# driver_03_12_2018.net
KiCad netlist of a schematic drawn in EAGLE
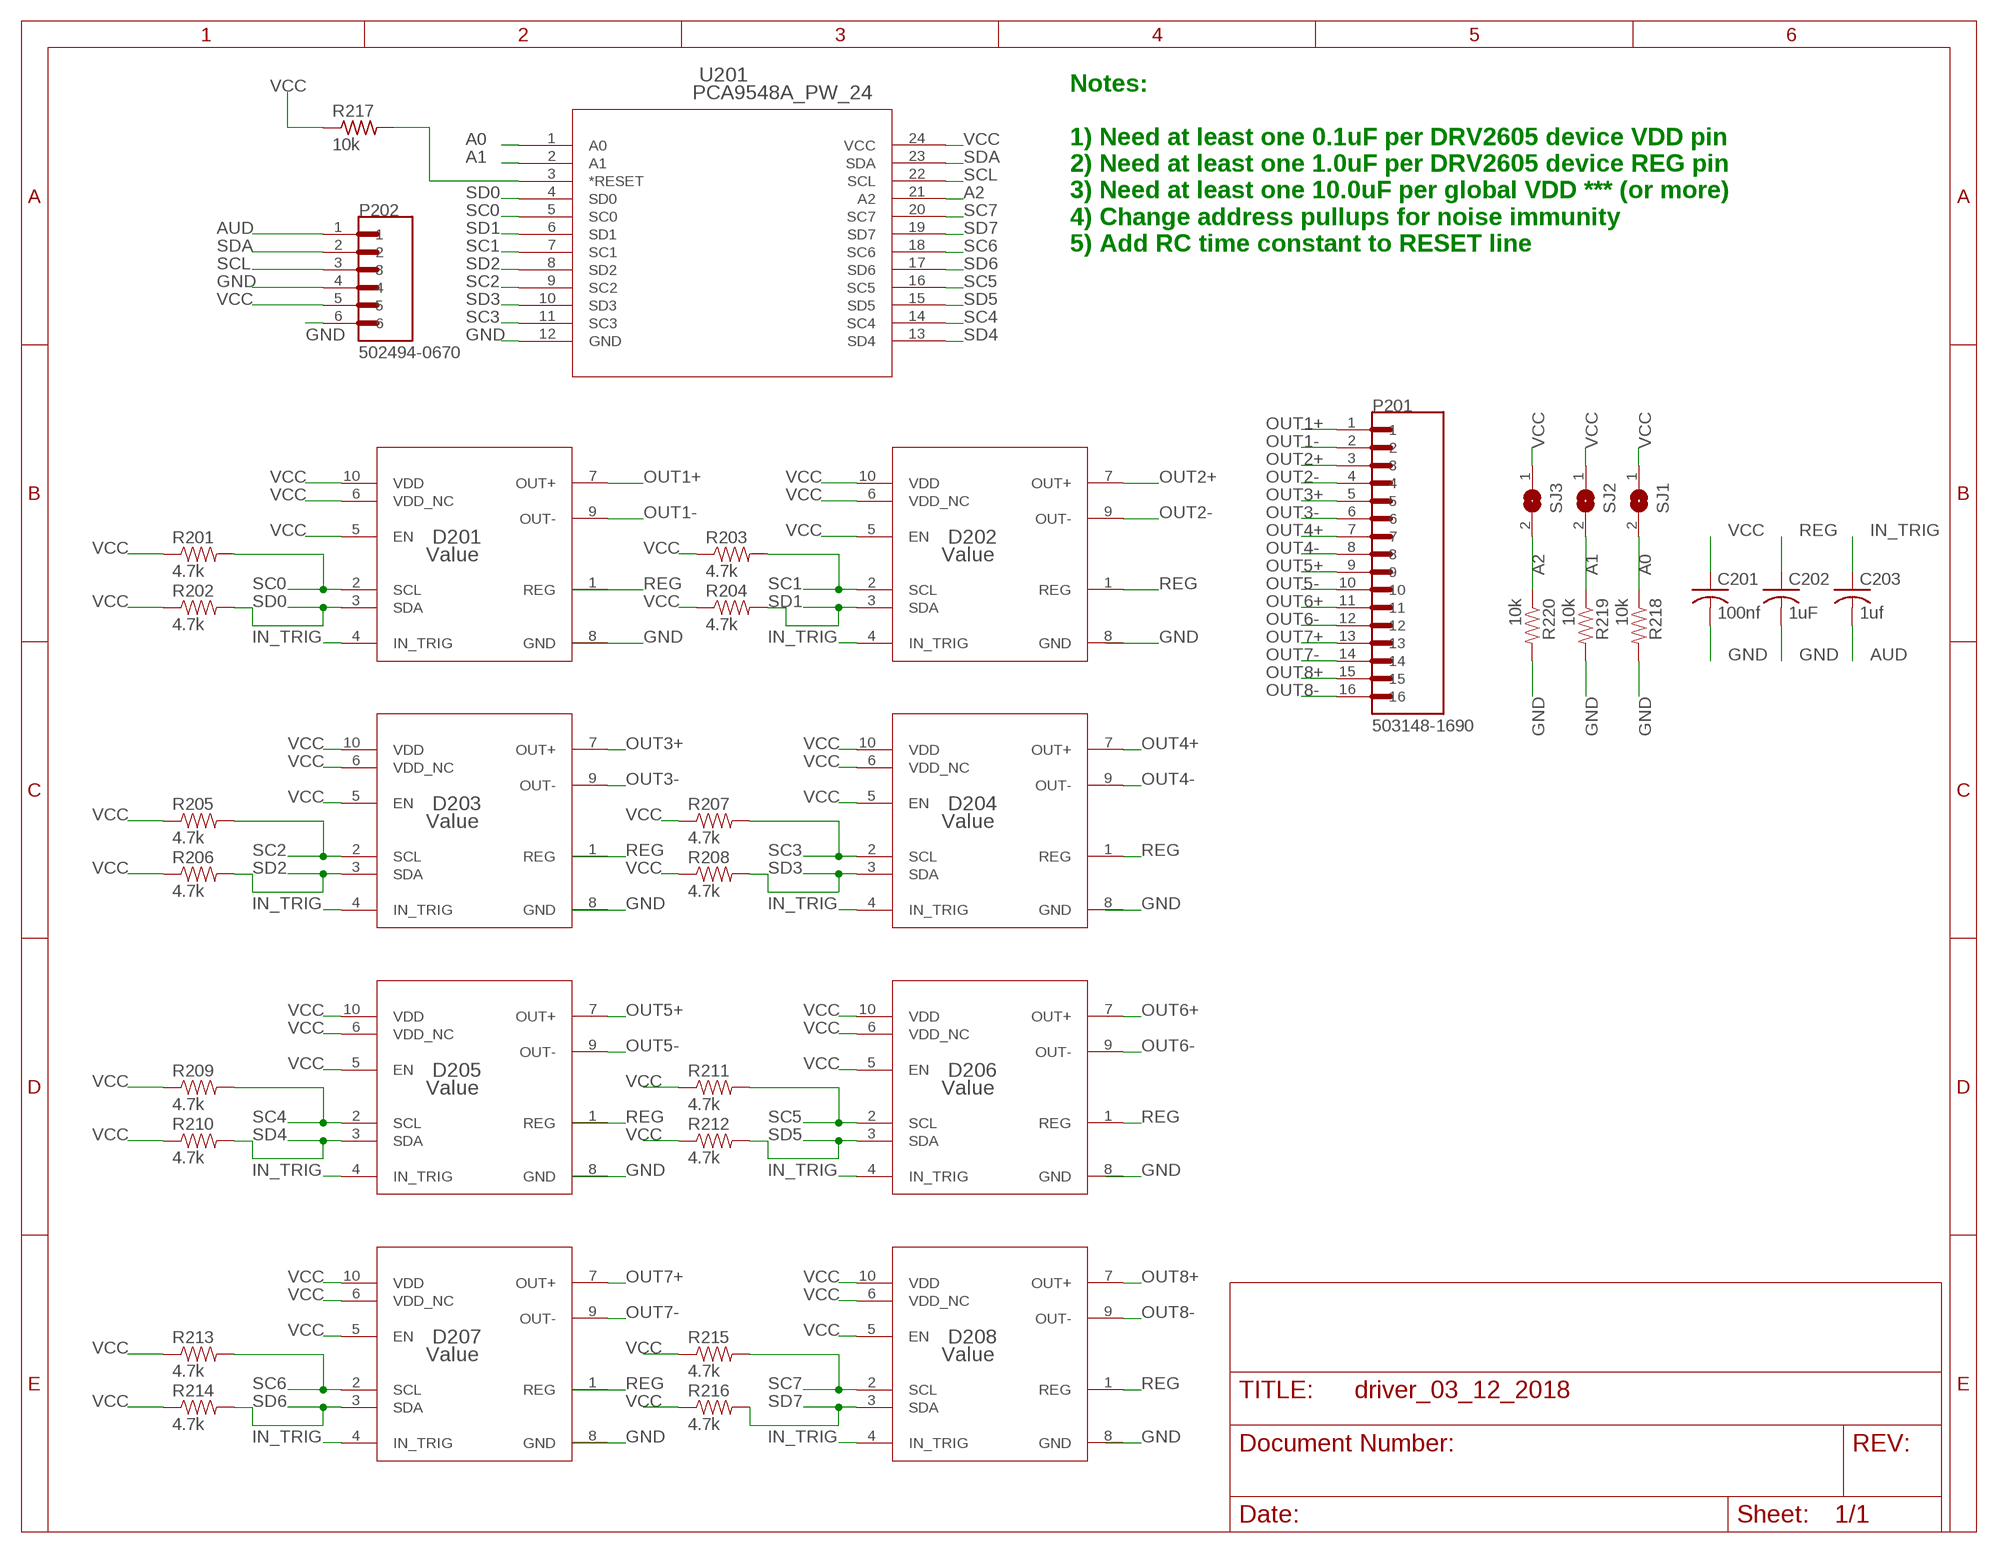
[diagram p0: schematic, sheet 1]

(export (version "E")
  (design (tool "Eeschema 10.0.6"))
  (components
    (comp (ref "C201")
      (value "100nf")
      (footprint "eagle-import:C0603")
      (libsource (lib "eagle-import") (part "C-USC0603"))
    )
    (comp (ref "C202")
      (value "1uF")
      (footprint "eagle-import:C0603")
      (libsource (lib "eagle-import") (part "C-USC0603"))
    )
    (comp (ref "C203")
      (value "1uf")
      (footprint "eagle-import:C0603")
      (libsource (lib "eagle-import") (part "C-USC0603"))
    )
    (comp (ref "D201")
      (value "Value")
      (footprint "eagle-import:DGS0010A")
      (fields (field (name "MANUFACTURER") "Texas Instruments") (field (name "PARTNUMBER") "DRV2605LDGS"))
      (libsource (lib "eagle-import") (part "DRV2605LDGSR"))
    )
    (comp (ref "D202")
      (value "Value")
      (footprint "eagle-import:DGS0010A")
      (fields (field (name "MANUFACTURER") "Texas Instruments") (field (name "PARTNUMBER") "DRV2605LDGS"))
      (libsource (lib "eagle-import") (part "DRV2605LDGSR"))
    )
    (comp (ref "D203")
      (value "Value")
      (footprint "eagle-import:DGS0010A")
      (fields (field (name "MANUFACTURER") "Texas Instruments") (field (name "PARTNUMBER") "DRV2605LDGS"))
      (libsource (lib "eagle-import") (part "DRV2605LDGSR"))
    )
    (comp (ref "D204")
      (value "Value")
      (footprint "eagle-import:DGS0010A")
      (fields (field (name "MANUFACTURER") "Texas Instruments") (field (name "PARTNUMBER") "DRV2605LDGS"))
      (libsource (lib "eagle-import") (part "DRV2605LDGSR"))
    )
    (comp (ref "D205")
      (value "Value")
      (footprint "eagle-import:DGS0010A")
      (fields (field (name "MANUFACTURER") "Texas Instruments") (field (name "PARTNUMBER") "DRV2605LDGS"))
      (libsource (lib "eagle-import") (part "DRV2605LDGSR"))
    )
    (comp (ref "D206")
      (value "Value")
      (footprint "eagle-import:DGS0010A")
      (fields (field (name "MANUFACTURER") "Texas Instruments") (field (name "PARTNUMBER") "DRV2605LDGS"))
      (libsource (lib "eagle-import") (part "DRV2605LDGSR"))
    )
    (comp (ref "D207")
      (value "Value")
      (footprint "eagle-import:DGS0010A")
      (fields (field (name "MANUFACTURER") "Texas Instruments") (field (name "PARTNUMBER") "DRV2605LDGS"))
      (libsource (lib "eagle-import") (part "DRV2605LDGSR"))
    )
    (comp (ref "D208")
      (value "Value")
      (footprint "eagle-import:DGS0010A")
      (fields (field (name "MANUFACTURER") "Texas Instruments") (field (name "PARTNUMBER") "DRV2605LDGS"))
      (libsource (lib "eagle-import") (part "DRV2605LDGSR"))
    )
    (comp (ref "P201")
      (value "503148-1690")
      (footprint "eagle-import:MOLEX_503148-1690")
      (fields (field (name "MF") "Molex"))
      (libsource (lib "eagle-import") (part "503148-1690"))
    )
    (comp (ref "P202")
      (value "502494-0670")
      (footprint "eagle-import:MOLEX_502494-0670")
      (fields (field (name "MF") "Molex"))
      (libsource (lib "eagle-import") (part "502494-0670"))
    )
    (comp (ref "R201")
      (value "4.7k")
      (footprint "eagle-import:EIA-0402")
      (libsource (lib "eagle-import") (part "RESISTOR0402-TYP"))
    )
    (comp (ref "R202")
      (value "4.7k")
      (footprint "eagle-import:EIA-0402")
      (libsource (lib "eagle-import") (part "RESISTOR0402-TYP"))
    )
    (comp (ref "R203")
      (value "4.7k")
      (footprint "eagle-import:EIA-0402")
      (libsource (lib "eagle-import") (part "RESISTOR0402-TYP"))
    )
    (comp (ref "R204")
      (value "4.7k")
      (footprint "eagle-import:EIA-0402")
      (libsource (lib "eagle-import") (part "RESISTOR0402-TYP"))
    )
    (comp (ref "R205")
      (value "4.7k")
      (footprint "eagle-import:EIA-0402")
      (libsource (lib "eagle-import") (part "RESISTOR0402-TYP"))
    )
    (comp (ref "R206")
      (value "4.7k")
      (footprint "eagle-import:EIA-0402")
      (libsource (lib "eagle-import") (part "RESISTOR0402-TYP"))
    )
    (comp (ref "R207")
      (value "4.7k")
      (footprint "eagle-import:EIA-0402")
      (libsource (lib "eagle-import") (part "RESISTOR0402-TYP"))
    )
    (comp (ref "R208")
      (value "4.7k")
      (footprint "eagle-import:EIA-0402")
      (libsource (lib "eagle-import") (part "RESISTOR0402-TYP"))
    )
    (comp (ref "R209")
      (value "4.7k")
      (footprint "eagle-import:EIA-0402")
      (libsource (lib "eagle-import") (part "RESISTOR0402-TYP"))
    )
    (comp (ref "R210")
      (value "4.7k")
      (footprint "eagle-import:EIA-0402")
      (libsource (lib "eagle-import") (part "RESISTOR0402-TYP"))
    )
    (comp (ref "R211")
      (value "4.7k")
      (footprint "eagle-import:EIA-0402")
      (libsource (lib "eagle-import") (part "RESISTOR0402-TYP"))
    )
    (comp (ref "R212")
      (value "4.7k")
      (footprint "eagle-import:EIA-0402")
      (libsource (lib "eagle-import") (part "RESISTOR0402-TYP"))
    )
    (comp (ref "R213")
      (value "4.7k")
      (footprint "eagle-import:EIA-0402")
      (libsource (lib "eagle-import") (part "RESISTOR0402-TYP"))
    )
    (comp (ref "R214")
      (value "4.7k")
      (footprint "eagle-import:EIA-0402")
      (libsource (lib "eagle-import") (part "RESISTOR0402-TYP"))
    )
    (comp (ref "R215")
      (value "4.7k")
      (footprint "eagle-import:EIA-0402")
      (libsource (lib "eagle-import") (part "RESISTOR0402-TYP"))
    )
    (comp (ref "R216")
      (value "4.7k")
      (footprint "eagle-import:EIA-0402")
      (libsource (lib "eagle-import") (part "RESISTOR0402-TYP"))
    )
    (comp (ref "R217")
      (value "10k")
      (footprint "eagle-import:R0402")
      (libsource (lib "eagle-import") (part "R-US_R0402"))
    )
    (comp (ref "R218")
      (value "10k")
      (footprint "eagle-import:EIA-0402")
      (libsource (lib "eagle-import") (part "RESISTOR0402-TYP"))
    )
    (comp (ref "R219")
      (value "10k")
      (footprint "eagle-import:EIA-0402")
      (libsource (lib "eagle-import") (part "RESISTOR0402-TYP"))
    )
    (comp (ref "R220")
      (value "10k")
      (footprint "eagle-import:EIA-0402")
      (libsource (lib "eagle-import") (part "RESISTOR0402-TYP"))
    )
    (comp (ref "SJ1") (value "SJ") (footprint "eagle-import:SJ") (libsource (lib "eagle-import") (part "SJ")))
    (comp (ref "SJ2") (value "SJ") (footprint "eagle-import:SJ") (libsource (lib "eagle-import") (part "SJ")))
    (comp (ref "SJ3") (value "SJ") (footprint "eagle-import:SJ") (libsource (lib "eagle-import") (part "SJ")))
    (comp (ref "U201")
      (value "PCA9548A_PW_24")
      (footprint "eagle-import:PW24")
      (fields
        (field (name "GENERIC_PART_NUMBER") "PCA9548A")
        (field (name "MANUFACTURER") "Texas Instruments")
        (field (name "MANUFACTURER_PART_NUMBER") "pca9548a_pw_24")
      )
      (libsource (lib "eagle-import") (part "PCA9548A_PW_24"))
    )
  )
  (nets
    (net (code "1") (name "/A0") (class "Default")
      (node (ref "R218") (pin "1") (pinfunction "1_1") (pintype "passive"))
      (node (ref "SJ1") (pin "2") (pinfunction "2_2") (pintype "passive"))
      (node (ref "U201") (pin "1") (pinfunction "A0_1") (pintype "input"))
    )
    (net (code "2") (name "/A1") (class "Default")
      (node (ref "R219") (pin "1") (pinfunction "1_1") (pintype "passive"))
      (node (ref "SJ2") (pin "2") (pinfunction "2_2") (pintype "passive"))
      (node (ref "U201") (pin "2") (pinfunction "A1_2") (pintype "input"))
    )
    (net (code "3") (name "/A2") (class "Default")
      (node (ref "R220") (pin "1") (pinfunction "1_1") (pintype "passive"))
      (node (ref "SJ3") (pin "2") (pinfunction "2_2") (pintype "passive"))
      (node (ref "U201") (pin "21") (pinfunction "A2_21") (pintype "input"))
    )
    (net (code "4") (name "/AUD") (class "Default")
      (node (ref "C203") (pin "2") (pinfunction "2_2") (pintype "passive"))
      (node (ref "P202") (pin "1") (pinfunction "1_1") (pintype "passive"))
    )
    (net (code "5") (name "/GND") (class "Default")
      (node (ref "C201") (pin "2") (pinfunction "2_2") (pintype "passive"))
      (node (ref "C202") (pin "2") (pinfunction "2_2") (pintype "passive"))
      (node (ref "D201") (pin "8") (pinfunction "GND_8") (pintype "power_in"))
      (node (ref "D202") (pin "8") (pinfunction "GND_8") (pintype "power_in"))
      (node (ref "D203") (pin "8") (pinfunction "GND_8") (pintype "power_in"))
      (node (ref "D204") (pin "8") (pinfunction "GND_8") (pintype "power_in"))
      (node (ref "D205") (pin "8") (pinfunction "GND_8") (pintype "power_in"))
      (node (ref "D206") (pin "8") (pinfunction "GND_8") (pintype "power_in"))
      (node (ref "D207") (pin "8") (pinfunction "GND_8") (pintype "power_in"))
      (node (ref "D208") (pin "8") (pinfunction "GND_8") (pintype "power_in"))
      (node (ref "P202") (pin "4") (pinfunction "4_4") (pintype "passive"))
      (node (ref "P202") (pin "6") (pinfunction "6_6") (pintype "passive"))
      (node (ref "R218") (pin "2") (pinfunction "2_2") (pintype "passive"))
      (node (ref "R219") (pin "2") (pinfunction "2_2") (pintype "passive"))
      (node (ref "R220") (pin "2") (pinfunction "2_2") (pintype "passive"))
      (node (ref "U201") (pin "12") (pinfunction "GND_12") (pintype "power_in"))
    )
    (net (code "6") (name "/IN_TRIG") (class "Default")
      (node (ref "C203") (pin "1") (pinfunction "1_1") (pintype "passive"))
      (node (ref "D201") (pin "4") (pinfunction "IN_TRIG_4") (pintype "input"))
      (node (ref "D202") (pin "4") (pinfunction "IN_TRIG_4") (pintype "input"))
      (node (ref "D203") (pin "4") (pinfunction "IN_TRIG_4") (pintype "input"))
      (node (ref "D204") (pin "4") (pinfunction "IN_TRIG_4") (pintype "input"))
      (node (ref "D205") (pin "4") (pinfunction "IN_TRIG_4") (pintype "input"))
      (node (ref "D206") (pin "4") (pinfunction "IN_TRIG_4") (pintype "input"))
      (node (ref "D207") (pin "4") (pinfunction "IN_TRIG_4") (pintype "input"))
      (node (ref "D208") (pin "4") (pinfunction "IN_TRIG_4") (pintype "input"))
    )
    (net (code "7") (name "/OUT1+") (class "Default")
      (node (ref "D201") (pin "7") (pinfunction "OUT+_7") (pintype "output"))
      (node (ref "P201") (pin "1") (pinfunction "1_1") (pintype "passive"))
    )
    (net (code "8") (name "/OUT1-") (class "Default")
      (node (ref "D201") (pin "9") (pinfunction "OUT-_9") (pintype "output"))
      (node (ref "P201") (pin "2") (pinfunction "2_2") (pintype "passive"))
    )
    (net (code "9") (name "/OUT2+") (class "Default")
      (node (ref "D202") (pin "7") (pinfunction "OUT+_7") (pintype "output"))
      (node (ref "P201") (pin "3") (pinfunction "3_3") (pintype "passive"))
    )
    (net (code "10") (name "/OUT2-") (class "Default")
      (node (ref "D202") (pin "9") (pinfunction "OUT-_9") (pintype "output"))
      (node (ref "P201") (pin "4") (pinfunction "4_4") (pintype "passive"))
    )
    (net (code "11") (name "/OUT3+") (class "Default")
      (node (ref "D203") (pin "7") (pinfunction "OUT+_7") (pintype "output"))
      (node (ref "P201") (pin "5") (pinfunction "5_5") (pintype "passive"))
    )
    (net (code "12") (name "/OUT3-") (class "Default")
      (node (ref "D203") (pin "9") (pinfunction "OUT-_9") (pintype "output"))
      (node (ref "P201") (pin "6") (pinfunction "6_6") (pintype "passive"))
    )
    (net (code "13") (name "/OUT4+") (class "Default")
      (node (ref "D204") (pin "7") (pinfunction "OUT+_7") (pintype "output"))
      (node (ref "P201") (pin "7") (pinfunction "7_7") (pintype "passive"))
    )
    (net (code "14") (name "/OUT4-") (class "Default")
      (node (ref "D204") (pin "9") (pinfunction "OUT-_9") (pintype "output"))
      (node (ref "P201") (pin "8") (pinfunction "8_8") (pintype "passive"))
    )
    (net (code "15") (name "/OUT5+") (class "Default")
      (node (ref "D205") (pin "7") (pinfunction "OUT+_7") (pintype "output"))
      (node (ref "P201") (pin "9") (pinfunction "9_9") (pintype "passive"))
    )
    (net (code "16") (name "/OUT5-") (class "Default")
      (node (ref "D205") (pin "9") (pinfunction "OUT-_9") (pintype "output"))
      (node (ref "P201") (pin "10") (pinfunction "10_10") (pintype "passive"))
    )
    (net (code "17") (name "/OUT6+") (class "Default")
      (node (ref "D206") (pin "7") (pinfunction "OUT+_7") (pintype "output"))
      (node (ref "P201") (pin "11") (pinfunction "11_11") (pintype "passive"))
    )
    (net (code "18") (name "/OUT6-") (class "Default")
      (node (ref "D206") (pin "9") (pinfunction "OUT-_9") (pintype "output"))
      (node (ref "P201") (pin "12") (pinfunction "12_12") (pintype "passive"))
    )
    (net (code "19") (name "/OUT7+") (class "Default")
      (node (ref "D207") (pin "7") (pinfunction "OUT+_7") (pintype "output"))
      (node (ref "P201") (pin "13") (pinfunction "13_13") (pintype "passive"))
    )
    (net (code "20") (name "/OUT7-") (class "Default")
      (node (ref "D207") (pin "9") (pinfunction "OUT-_9") (pintype "output"))
      (node (ref "P201") (pin "14") (pinfunction "14_14") (pintype "passive"))
    )
    (net (code "21") (name "/OUT8+") (class "Default")
      (node (ref "D208") (pin "7") (pinfunction "OUT+_7") (pintype "output"))
      (node (ref "P201") (pin "15") (pinfunction "15_15") (pintype "passive"))
    )
    (net (code "22") (name "/OUT8-") (class "Default")
      (node (ref "D208") (pin "9") (pinfunction "OUT-_9") (pintype "output"))
      (node (ref "P201") (pin "16") (pinfunction "16_16") (pintype "passive"))
    )
    (net (code "23") (name "/REG") (class "Default")
      (node (ref "C202") (pin "1") (pinfunction "1_1") (pintype "passive"))
      (node (ref "D201") (pin "1") (pinfunction "REG_1") (pintype "power_in"))
      (node (ref "D202") (pin "1") (pinfunction "REG_1") (pintype "power_in"))
      (node (ref "D203") (pin "1") (pinfunction "REG_1") (pintype "power_in"))
      (node (ref "D204") (pin "1") (pinfunction "REG_1") (pintype "power_in"))
      (node (ref "D205") (pin "1") (pinfunction "REG_1") (pintype "power_in"))
      (node (ref "D206") (pin "1") (pinfunction "REG_1") (pintype "power_in"))
      (node (ref "D207") (pin "1") (pinfunction "REG_1") (pintype "power_in"))
      (node (ref "D208") (pin "1") (pinfunction "REG_1") (pintype "power_in"))
    )
    (net (code "24") (name "/SC0") (class "Default")
      (node (ref "D201") (pin "2") (pinfunction "SCL_2") (pintype "input"))
      (node (ref "R201") (pin "2") (pinfunction "2_2") (pintype "passive"))
      (node (ref "U201") (pin "5") (pinfunction "SC0_5") (pintype "passive"))
    )
    (net (code "25") (name "/SC1") (class "Default")
      (node (ref "D202") (pin "2") (pinfunction "SCL_2") (pintype "input"))
      (node (ref "R203") (pin "2") (pinfunction "2_2") (pintype "passive"))
      (node (ref "U201") (pin "7") (pinfunction "SC1_7") (pintype "passive"))
    )
    (net (code "26") (name "/SC2") (class "Default")
      (node (ref "D203") (pin "2") (pinfunction "SCL_2") (pintype "input"))
      (node (ref "R205") (pin "2") (pinfunction "2_2") (pintype "passive"))
      (node (ref "U201") (pin "9") (pinfunction "SC2_9") (pintype "passive"))
    )
    (net (code "27") (name "/SC3") (class "Default")
      (node (ref "D204") (pin "2") (pinfunction "SCL_2") (pintype "input"))
      (node (ref "R207") (pin "2") (pinfunction "2_2") (pintype "passive"))
      (node (ref "U201") (pin "11") (pinfunction "SC3_11") (pintype "passive"))
    )
    (net (code "28") (name "/SC4") (class "Default")
      (node (ref "D205") (pin "2") (pinfunction "SCL_2") (pintype "input"))
      (node (ref "R209") (pin "2") (pinfunction "2_2") (pintype "passive"))
      (node (ref "U201") (pin "14") (pinfunction "SC4_14") (pintype "passive"))
    )
    (net (code "29") (name "/SC5") (class "Default")
      (node (ref "D206") (pin "2") (pinfunction "SCL_2") (pintype "input"))
      (node (ref "R211") (pin "2") (pinfunction "2_2") (pintype "passive"))
      (node (ref "U201") (pin "16") (pinfunction "SC5_16") (pintype "passive"))
    )
    (net (code "30") (name "/SC6") (class "Default")
      (node (ref "D207") (pin "2") (pinfunction "SCL_2") (pintype "input"))
      (node (ref "R213") (pin "2") (pinfunction "2_2") (pintype "passive"))
      (node (ref "U201") (pin "18") (pinfunction "SC6_18") (pintype "passive"))
    )
    (net (code "31") (name "/SC7") (class "Default")
      (node (ref "D208") (pin "2") (pinfunction "SCL_2") (pintype "input"))
      (node (ref "R215") (pin "2") (pinfunction "2_2") (pintype "passive"))
      (node (ref "U201") (pin "20") (pinfunction "SC7_20") (pintype "passive"))
    )
    (net (code "32") (name "/SCL") (class "Default")
      (node (ref "P202") (pin "3") (pinfunction "3_3") (pintype "passive"))
      (node (ref "U201") (pin "22") (pinfunction "SCL_22") (pintype "passive"))
    )
    (net (code "33") (name "/SD0") (class "Default")
      (node (ref "D201") (pin "3") (pinfunction "SDA_3") (pintype "bidirectional"))
      (node (ref "R202") (pin "2") (pinfunction "2_2") (pintype "passive"))
      (node (ref "U201") (pin "4") (pinfunction "SD0_4") (pintype "passive"))
    )
    (net (code "34") (name "/SD1") (class "Default")
      (node (ref "D202") (pin "3") (pinfunction "SDA_3") (pintype "bidirectional"))
      (node (ref "R204") (pin "2") (pinfunction "2_2") (pintype "passive"))
      (node (ref "U201") (pin "6") (pinfunction "SD1_6") (pintype "passive"))
    )
    (net (code "35") (name "/SD2") (class "Default")
      (node (ref "D203") (pin "3") (pinfunction "SDA_3") (pintype "bidirectional"))
      (node (ref "R206") (pin "2") (pinfunction "2_2") (pintype "passive"))
      (node (ref "U201") (pin "8") (pinfunction "SD2_8") (pintype "passive"))
    )
    (net (code "36") (name "/SD3") (class "Default")
      (node (ref "D204") (pin "3") (pinfunction "SDA_3") (pintype "bidirectional"))
      (node (ref "R208") (pin "2") (pinfunction "2_2") (pintype "passive"))
      (node (ref "U201") (pin "10") (pinfunction "SD3_10") (pintype "passive"))
    )
    (net (code "37") (name "/SD4") (class "Default")
      (node (ref "D205") (pin "3") (pinfunction "SDA_3") (pintype "bidirectional"))
      (node (ref "R210") (pin "2") (pinfunction "2_2") (pintype "passive"))
      (node (ref "U201") (pin "13") (pinfunction "SD4_13") (pintype "passive"))
    )
    (net (code "38") (name "/SD5") (class "Default")
      (node (ref "D206") (pin "3") (pinfunction "SDA_3") (pintype "bidirectional"))
      (node (ref "R212") (pin "2") (pinfunction "2_2") (pintype "passive"))
      (node (ref "U201") (pin "15") (pinfunction "SD5_15") (pintype "passive"))
    )
    (net (code "39") (name "/SD6") (class "Default")
      (node (ref "D207") (pin "3") (pinfunction "SDA_3") (pintype "bidirectional"))
      (node (ref "R214") (pin "2") (pinfunction "2_2") (pintype "passive"))
      (node (ref "U201") (pin "17") (pinfunction "SD6_17") (pintype "passive"))
    )
    (net (code "40") (name "/SD7") (class "Default")
      (node (ref "D208") (pin "3") (pinfunction "SDA_3") (pintype "bidirectional"))
      (node (ref "R216") (pin "2") (pinfunction "2_2") (pintype "passive"))
      (node (ref "U201") (pin "19") (pinfunction "SD7_19") (pintype "passive"))
    )
    (net (code "41") (name "/SDA") (class "Default")
      (node (ref "P202") (pin "2") (pinfunction "2_2") (pintype "passive"))
      (node (ref "U201") (pin "23") (pinfunction "SDA_23") (pintype "passive"))
    )
    (net (code "42") (name "/VCC") (class "Default")
      (node (ref "C201") (pin "1") (pinfunction "1_1") (pintype "passive"))
      (node (ref "D201") (pin "10") (pinfunction "VDD_10") (pintype "power_in"))
      (node (ref "D201") (pin "5") (pinfunction "EN_5") (pintype "input"))
      (node (ref "D201") (pin "6") (pinfunction "VDD_NC_6") (pintype "power_in"))
      (node (ref "D202") (pin "10") (pinfunction "VDD_10") (pintype "power_in"))
      (node (ref "D202") (pin "5") (pinfunction "EN_5") (pintype "input"))
      (node (ref "D202") (pin "6") (pinfunction "VDD_NC_6") (pintype "power_in"))
      (node (ref "D203") (pin "10") (pinfunction "VDD_10") (pintype "power_in"))
      (node (ref "D203") (pin "5") (pinfunction "EN_5") (pintype "input"))
      (node (ref "D203") (pin "6") (pinfunction "VDD_NC_6") (pintype "power_in"))
      (node (ref "D204") (pin "10") (pinfunction "VDD_10") (pintype "power_in"))
      (node (ref "D204") (pin "5") (pinfunction "EN_5") (pintype "input"))
      (node (ref "D204") (pin "6") (pinfunction "VDD_NC_6") (pintype "power_in"))
      (node (ref "D205") (pin "10") (pinfunction "VDD_10") (pintype "power_in"))
      (node (ref "D205") (pin "5") (pinfunction "EN_5") (pintype "input"))
      (node (ref "D205") (pin "6") (pinfunction "VDD_NC_6") (pintype "power_in"))
      (node (ref "D206") (pin "10") (pinfunction "VDD_10") (pintype "power_in"))
      (node (ref "D206") (pin "5") (pinfunction "EN_5") (pintype "input"))
      (node (ref "D206") (pin "6") (pinfunction "VDD_NC_6") (pintype "power_in"))
      (node (ref "D207") (pin "10") (pinfunction "VDD_10") (pintype "power_in"))
      (node (ref "D207") (pin "5") (pinfunction "EN_5") (pintype "input"))
      (node (ref "D207") (pin "6") (pinfunction "VDD_NC_6") (pintype "power_in"))
      (node (ref "D208") (pin "10") (pinfunction "VDD_10") (pintype "power_in"))
      (node (ref "D208") (pin "5") (pinfunction "EN_5") (pintype "input"))
      (node (ref "D208") (pin "6") (pinfunction "VDD_NC_6") (pintype "power_in"))
      (node (ref "P202") (pin "5") (pinfunction "5_5") (pintype "passive"))
      (node (ref "R201") (pin "1") (pinfunction "1_1") (pintype "passive"))
      (node (ref "R202") (pin "1") (pinfunction "1_1") (pintype "passive"))
      (node (ref "R203") (pin "1") (pinfunction "1_1") (pintype "passive"))
      (node (ref "R204") (pin "1") (pinfunction "1_1") (pintype "passive"))
      (node (ref "R205") (pin "1") (pinfunction "1_1") (pintype "passive"))
      (node (ref "R206") (pin "1") (pinfunction "1_1") (pintype "passive"))
      (node (ref "R207") (pin "1") (pinfunction "1_1") (pintype "passive"))
      (node (ref "R208") (pin "1") (pinfunction "1_1") (pintype "passive"))
      (node (ref "R209") (pin "1") (pinfunction "1_1") (pintype "passive"))
      (node (ref "R210") (pin "1") (pinfunction "1_1") (pintype "passive"))
      (node (ref "R211") (pin "1") (pinfunction "1_1") (pintype "passive"))
      (node (ref "R212") (pin "1") (pinfunction "1_1") (pintype "passive"))
      (node (ref "R213") (pin "1") (pinfunction "1_1") (pintype "passive"))
      (node (ref "R214") (pin "1") (pinfunction "1_1") (pintype "passive"))
      (node (ref "R215") (pin "1") (pinfunction "1_1") (pintype "passive"))
      (node (ref "R216") (pin "1") (pinfunction "1_1") (pintype "passive"))
      (node (ref "R217") (pin "1") (pinfunction "1_1") (pintype "passive"))
      (node (ref "SJ1") (pin "1") (pinfunction "1_1") (pintype "passive"))
      (node (ref "SJ2") (pin "1") (pinfunction "1_1") (pintype "passive"))
      (node (ref "SJ3") (pin "1") (pinfunction "1_1") (pintype "passive"))
      (node (ref "U201") (pin "24") (pinfunction "VCC_24") (pintype "power_in"))
    )
    (net (code "43") (name "Net-(U201-*RESET)") (class "Default")
      (node (ref "R217") (pin "2") (pinfunction "2_2") (pintype "passive"))
      (node (ref "U201") (pin "3") (pinfunction "*RESET_3") (pintype "input"))
    )
  )
)
